# SDC_1.net
KiCad netlist of a schematic drawn in Altium Designer
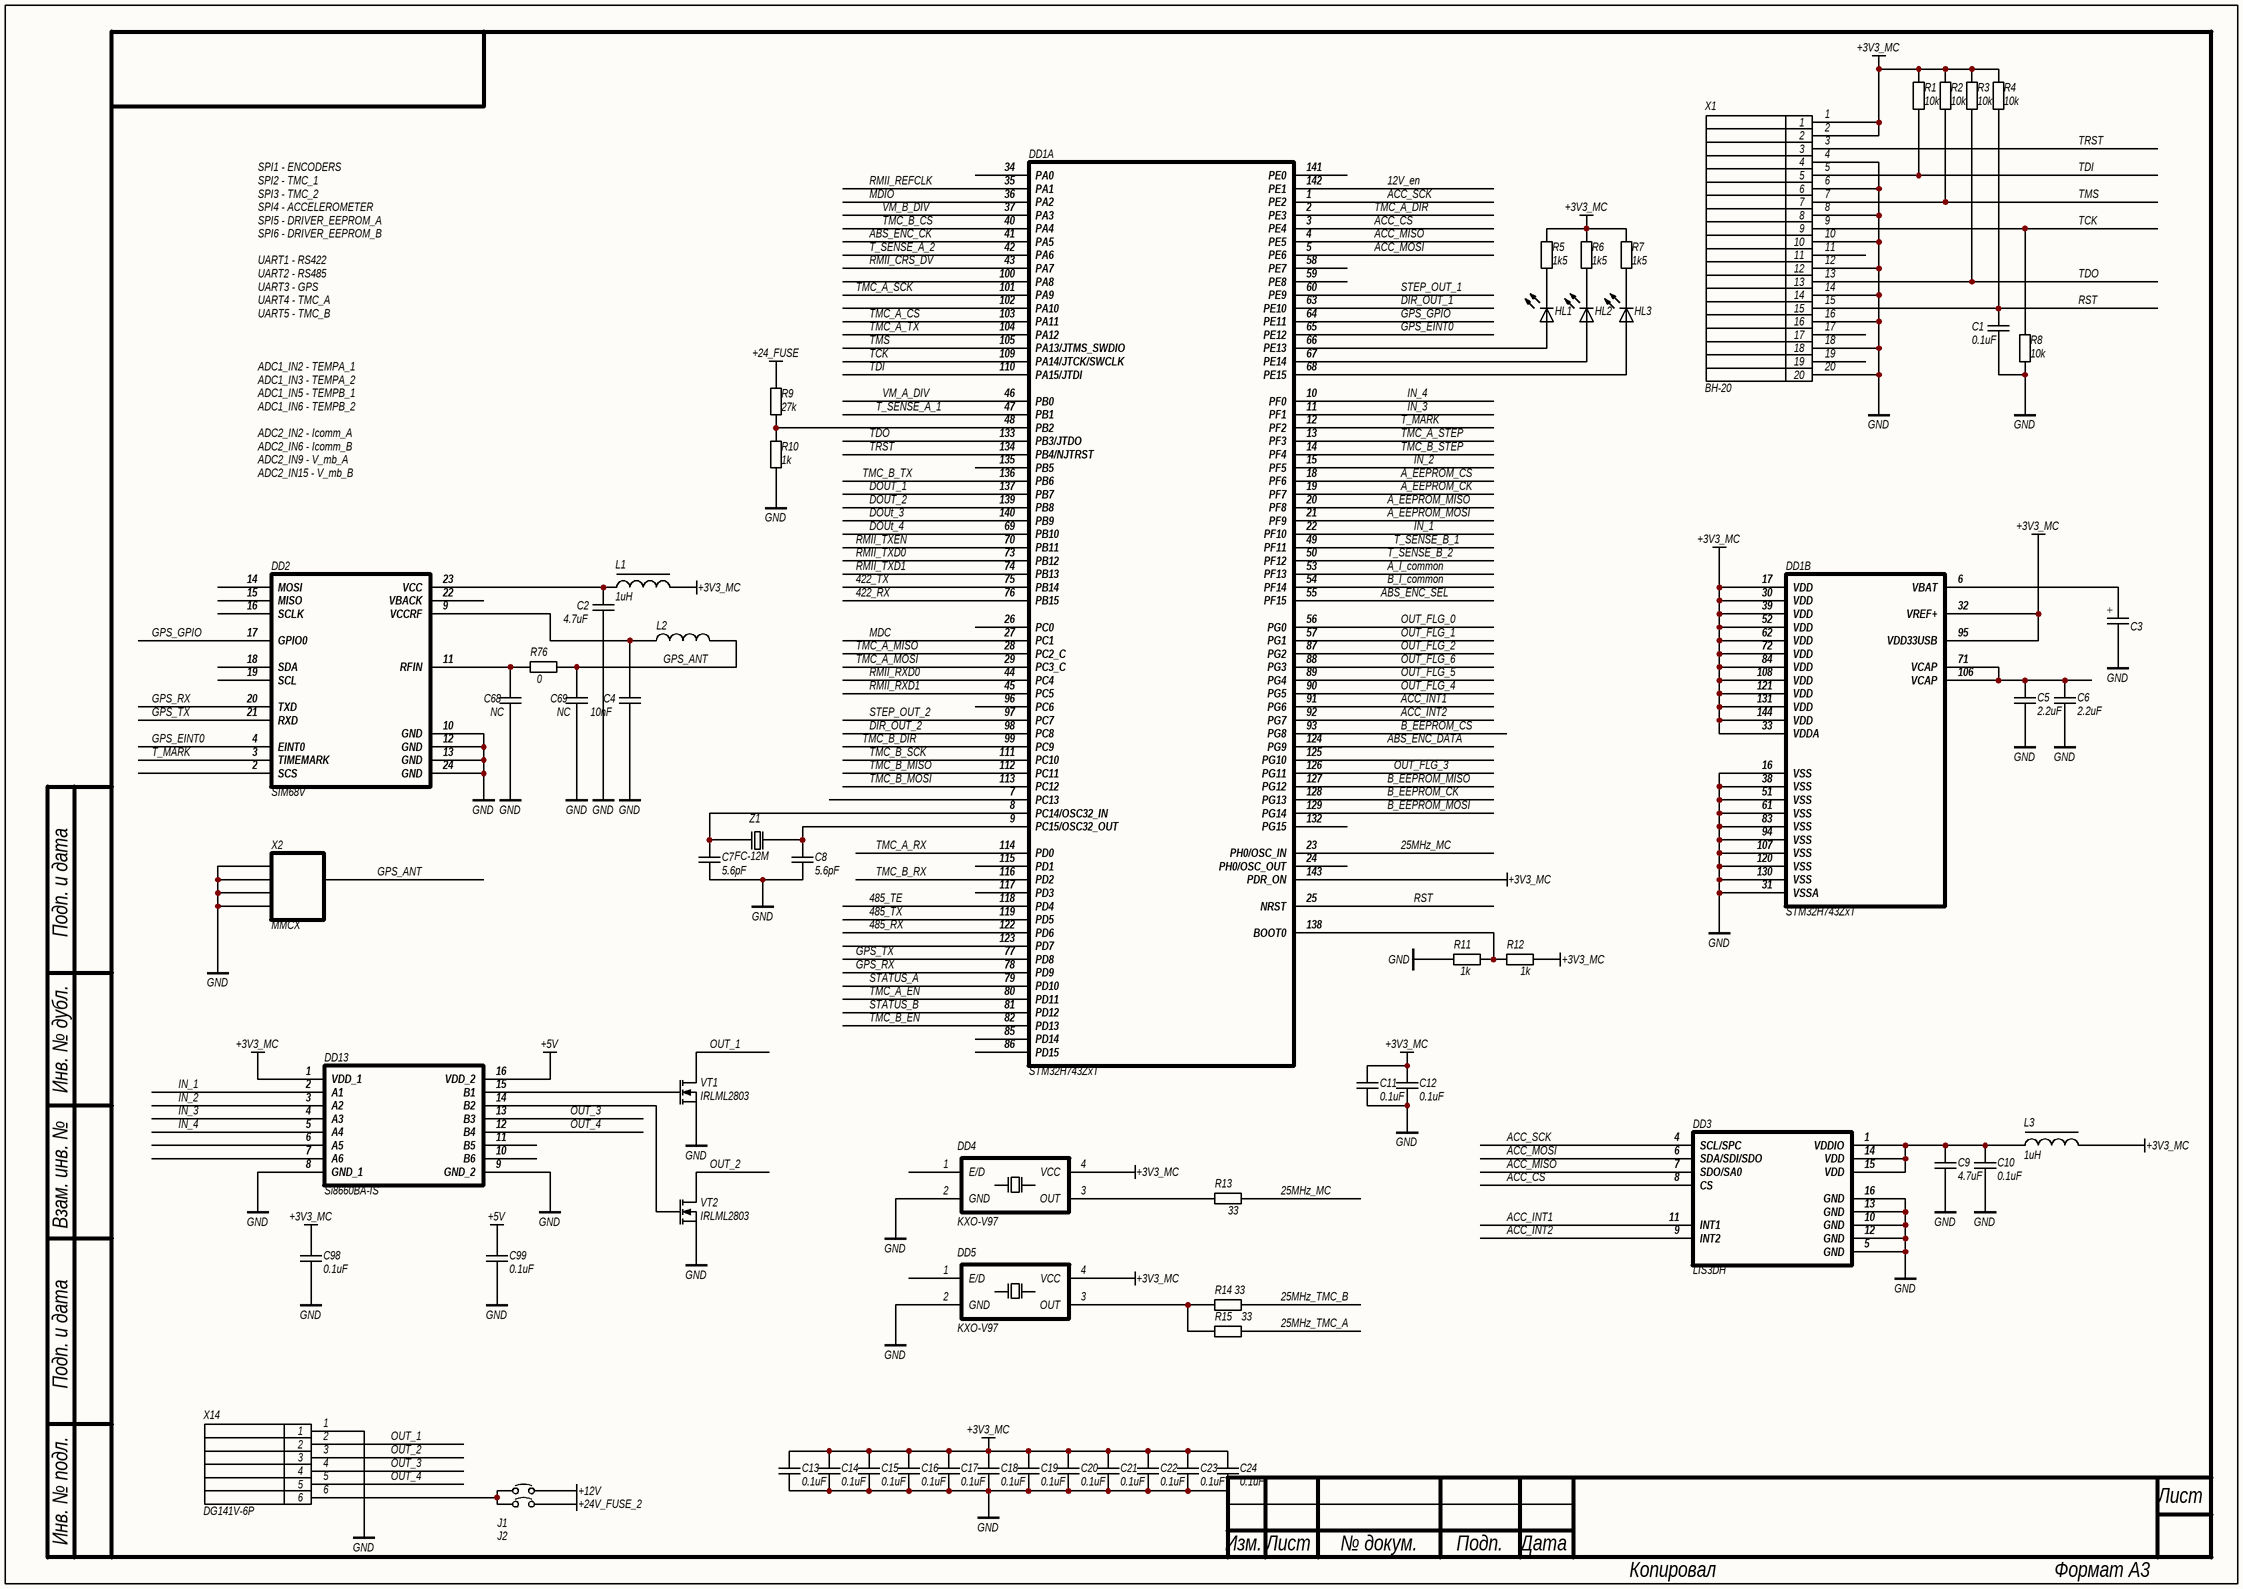
[diagram p0: SDC_1.SchDoc]

(export (version "E")
  (design (tool "Eeschema 10.0.6"))
  (components
    (comp (ref "C1")
      (value "0.1uF")
      (footprint "C0603")
      (description "SMD Capacitor")
      (fields (field (name "MANUFACTURER") "Murata") (field (name "TOLERANCE") "10%"))
      (libsource (lib "VKA") (part "CAP"))
    )
    (comp (ref "C2")
      (value "4.7uF")
      (footprint "C0603")
      (description "SMD Capacitor")
      (fields (field (name "MANUFACTURER") "Murata") (field (name "TOLERANCE") "10%"))
      (libsource (lib "VKA") (part "CAP"))
    )
    (comp (ref "C3")
      (value "KR-5R5H155-R")
      (footprint "KR-5R5H155-R")
      (description "Ionistor")
      (fields (field (name "MANUFACTURER") "Murata") (field (name "VOLTAGE") "5V"))
      (libsource (lib "VKA") (part "KR-5R5H155-R"))
    )
    (comp (ref "C4")
      (value "10nF")
      (footprint "C0603")
      (description "SMD Capacitor")
      (fields (field (name "MANUFACTURER") "Murata") (field (name "TOLERANCE") "10%"))
      (libsource (lib "VKA") (part "CAP"))
    )
    (comp (ref "C5")
      (value "2.2uF")
      (footprint "C0603")
      (description "SMD Capacitor")
      (fields (field (name "MANUFACTURER") "Murata") (field (name "TOLERANCE") "10%"))
      (libsource (lib "VKA") (part "CAP"))
    )
    (comp (ref "C6")
      (value "2.2uF")
      (footprint "C0603")
      (description "SMD Capacitor")
      (fields (field (name "MANUFACTURER") "Murata") (field (name "TOLERANCE") "10%"))
      (libsource (lib "VKA") (part "CAP"))
    )
    (comp (ref "C7")
      (value "5.6pF")
      (footprint "C0603")
      (description "SMD Capacitor")
      (fields (field (name "MANUFACTURER") "Murata") (field (name "TOLERANCE") "10%"))
      (libsource (lib "VKA") (part "CAP"))
    )
    (comp (ref "C8")
      (value "5.6pF")
      (footprint "C0603")
      (description "SMD Capacitor")
      (fields (field (name "MANUFACTURER") "Murata") (field (name "TOLERANCE") "10%"))
      (libsource (lib "VKA") (part "CAP"))
    )
    (comp (ref "C9")
      (value "4.7uF")
      (footprint "C0603")
      (description "SMD Capacitor")
      (fields (field (name "MANUFACTURER") "Murata") (field (name "TOLERANCE") "10%"))
      (libsource (lib "VKA") (part "CAP"))
    )
    (comp (ref "C10")
      (value "0.1uF")
      (footprint "C0603")
      (description "SMD Capacitor")
      (fields (field (name "MANUFACTURER") "Murata") (field (name "TOLERANCE") "10%"))
      (libsource (lib "VKA") (part "CAP"))
    )
    (comp (ref "C11")
      (value "0.1uF")
      (footprint "C0603")
      (description "SMD Capacitor")
      (fields (field (name "MANUFACTURER") "Murata") (field (name "TOLERANCE") "10%"))
      (libsource (lib "VKA") (part "CAP"))
    )
    (comp (ref "C12")
      (value "0.1uF")
      (footprint "C0603")
      (description "SMD Capacitor")
      (fields (field (name "MANUFACTURER") "Murata") (field (name "TOLERANCE") "10%"))
      (libsource (lib "VKA") (part "CAP"))
    )
    (comp (ref "C13")
      (value "0.1uF")
      (footprint "C0603")
      (description "SMD Capacitor")
      (fields (field (name "MANUFACTURER") "Murata") (field (name "TOLERANCE") "10%"))
      (libsource (lib "VKA") (part "CAP"))
    )
    (comp (ref "C14")
      (value "0.1uF")
      (footprint "C0603")
      (description "SMD Capacitor")
      (fields (field (name "MANUFACTURER") "Murata") (field (name "TOLERANCE") "10%"))
      (libsource (lib "VKA") (part "CAP"))
    )
    (comp (ref "C15")
      (value "0.1uF")
      (footprint "C0603")
      (description "SMD Capacitor")
      (fields (field (name "MANUFACTURER") "Murata") (field (name "TOLERANCE") "10%"))
      (libsource (lib "VKA") (part "CAP"))
    )
    (comp (ref "C16")
      (value "0.1uF")
      (footprint "C0603")
      (description "SMD Capacitor")
      (fields (field (name "MANUFACTURER") "Murata") (field (name "TOLERANCE") "10%"))
      (libsource (lib "VKA") (part "CAP"))
    )
    (comp (ref "C17")
      (value "0.1uF")
      (footprint "C0603")
      (description "SMD Capacitor")
      (fields (field (name "MANUFACTURER") "Murata") (field (name "TOLERANCE") "10%"))
      (libsource (lib "VKA") (part "CAP"))
    )
    (comp (ref "C18")
      (value "0.1uF")
      (footprint "C0603")
      (description "SMD Capacitor")
      (fields (field (name "MANUFACTURER") "Murata") (field (name "TOLERANCE") "10%"))
      (libsource (lib "VKA") (part "CAP"))
    )
    (comp (ref "C19")
      (value "0.1uF")
      (footprint "C0603")
      (description "SMD Capacitor")
      (fields (field (name "MANUFACTURER") "Murata") (field (name "TOLERANCE") "10%"))
      (libsource (lib "VKA") (part "CAP"))
    )
    (comp (ref "C20")
      (value "0.1uF")
      (footprint "C0603")
      (description "SMD Capacitor")
      (fields (field (name "MANUFACTURER") "Murata") (field (name "TOLERANCE") "10%"))
      (libsource (lib "VKA") (part "CAP"))
    )
    (comp (ref "C21")
      (value "0.1uF")
      (footprint "C0603")
      (description "SMD Capacitor")
      (fields (field (name "MANUFACTURER") "Murata") (field (name "TOLERANCE") "10%"))
      (libsource (lib "VKA") (part "CAP"))
    )
    (comp (ref "C22")
      (value "0.1uF")
      (footprint "C0603")
      (description "SMD Capacitor")
      (fields (field (name "MANUFACTURER") "Murata") (field (name "TOLERANCE") "10%"))
      (libsource (lib "VKA") (part "CAP"))
    )
    (comp (ref "C23")
      (value "0.1uF")
      (footprint "C0603")
      (description "SMD Capacitor")
      (fields (field (name "MANUFACTURER") "Murata") (field (name "TOLERANCE") "10%"))
      (libsource (lib "VKA") (part "CAP"))
    )
    (comp (ref "C24")
      (value "0.1uF")
      (footprint "C0603")
      (description "SMD Capacitor")
      (fields (field (name "MANUFACTURER") "Murata") (field (name "TOLERANCE") "10%"))
      (libsource (lib "VKA") (part "CAP"))
    )
    (comp (ref "C68")
      (value "NC")
      (footprint "C0603")
      (description "SMD Capacitor")
      (fields (field (name "MANUFACTURER") "Murata") (field (name "TOLERANCE") "10%"))
      (libsource (lib "VKA") (part "CAP"))
    )
    (comp (ref "C69")
      (value "NC")
      (footprint "C0603")
      (description "SMD Capacitor")
      (fields (field (name "MANUFACTURER") "Murata") (field (name "TOLERANCE") "10%"))
      (libsource (lib "VKA") (part "CAP"))
    )
    (comp (ref "C98")
      (value "0.1uF")
      (footprint "C0603")
      (description "SMD Capacitor")
      (fields (field (name "MANUFACTURER") "Murata") (field (name "TOLERANCE") "10%"))
      (libsource (lib "VKA") (part "CAP"))
    )
    (comp (ref "C99")
      (value "0.1uF")
      (footprint "C0603")
      (description "SMD Capacitor")
      (fields (field (name "MANUFACTURER") "Murata") (field (name "TOLERANCE") "10%"))
      (libsource (lib "VKA") (part "CAP"))
    )
    (comp (ref "DD1")
      (value "STM32H743ZxT")
      (footprint "STM-LQFP144_L")
      (description "ARM Cortex-M7, 480MHz, 32-bit MCU+FPU, 144-pin LQFP")
      (libsource (lib "VKA") (part "STM32H743ZxT"))
    )
    (comp (ref "DD2")
      (value "SIM68V")
      (footprint "SIM68M")
      (description "GPS module")
      (libsource (lib "VKA") (part "SIM68V"))
    )
    (comp (ref "DD3")
      (value "LIS3DH")
      (footprint "LGA-16")
      (description "Accelerometer")
      (libsource (lib "VKA") (part "LIS3DH"))
    )
    (comp (ref "DD4")
      (value "KXO-V97")
      (footprint "SO4-GEN")
      (description "KXO generator")
      (libsource (lib "VKA") (part "KXO-V97"))
    )
    (comp (ref "DD5")
      (value "KXO-V97")
      (footprint "SO4-GEN")
      (description "KXO generator")
      (libsource (lib "VKA") (part "KXO-V97"))
    )
    (comp (ref "DD13")
      (value "Si8660BA-IS")
      (footprint "SO-16_N")
      (description "digital isolator")
      (libsource (lib "VKA") (part "Si8660BA-IS"))
    )
    (comp (ref "HL1") (value "LED0603") (footprint "LED0603") (libsource (lib "VKA") (part "LED0603")))
    (comp (ref "HL2") (value "LED0603") (footprint "LED0603") (libsource (lib "VKA") (part "LED0603")))
    (comp (ref "HL3") (value "LED0603") (footprint "LED0603") (libsource (lib "VKA") (part "LED0603")))
    (comp (ref "J1") (value "JUMP") (footprint "JUMP") (libsource (lib "VKA") (part "JUMP")))
    (comp (ref "J2") (value "JUMP") (footprint "JUMP") (libsource (lib "VKA") (part "JUMP")))
    (comp (ref "L1")
      (value "1uH")
      (footprint "LQH32CN")
      (description "chip inductor")
      (fields (field (name "Comment") "LQH32CN"))
      (libsource (lib "VKA") (part "LQH32CN"))
    )
    (comp (ref "L2")
      (value "FerriteBead")
      (footprint "L0603")
      (description "SMD Chip ferrite bead 0603")
      (libsource (lib "VKA") (part "FerriteBead"))
    )
    (comp (ref "L3")
      (value "1uH")
      (footprint "LQH32CN")
      (description "chip inductor")
      (fields (field (name "Comment") "LQH32CN"))
      (libsource (lib "VKA") (part "LQH32CN"))
    )
    (comp (ref "R1")
      (value "10k")
      (footprint "R0603")
      (description "SMD Resistor")
      (fields (field (name "POWER") "0.062 Wt") (field (name "TOLERANCE") "5%"))
      (libsource (lib "") (part "RES_1"))
    )
    (comp (ref "R2")
      (value "10k")
      (footprint "R0603")
      (description "SMD Resistor")
      (fields (field (name "POWER") "0.062 Wt") (field (name "TOLERANCE") "5%"))
      (libsource (lib "") (part "RES_1"))
    )
    (comp (ref "R3")
      (value "10k")
      (footprint "R0603")
      (description "SMD Resistor")
      (fields (field (name "POWER") "0.062 Wt") (field (name "TOLERANCE") "5%"))
      (libsource (lib "") (part "RES_1"))
    )
    (comp (ref "R4")
      (value "10k")
      (footprint "R0603")
      (description "SMD Resistor")
      (fields (field (name "POWER") "0.062 Wt") (field (name "TOLERANCE") "5%"))
      (libsource (lib "") (part "RES_1"))
    )
    (comp (ref "R5")
      (value "1k5")
      (footprint "R0603")
      (description "SMD Resistor")
      (fields (field (name "POWER") "0.062 Wt") (field (name "TOLERANCE") "5%"))
      (libsource (lib "") (part "RES_1"))
    )
    (comp (ref "R6")
      (value "1k5")
      (footprint "R0603")
      (description "SMD Resistor")
      (fields (field (name "POWER") "0.062 Wt") (field (name "TOLERANCE") "5%"))
      (libsource (lib "") (part "RES_1"))
    )
    (comp (ref "R7")
      (value "1k5")
      (footprint "R0603")
      (description "SMD Resistor")
      (fields (field (name "POWER") "0.062 Wt") (field (name "TOLERANCE") "5%"))
      (libsource (lib "") (part "RES_1"))
    )
    (comp (ref "R8")
      (value "10k")
      (footprint "R0603")
      (description "SMD Resistor")
      (fields (field (name "POWER") "0.062 Wt") (field (name "TOLERANCE") "5%"))
      (libsource (lib "") (part "RES_1"))
    )
    (comp (ref "R9")
      (value "27k")
      (footprint "R0603")
      (description "SMD Resistor")
      (fields (field (name "POWER") "0.062 Wt") (field (name "TOLERANCE") "5%"))
      (libsource (lib "") (part "RES_2"))
    )
    (comp (ref "R10")
      (value "1k")
      (footprint "R0603")
      (description "SMD Resistor")
      (fields (field (name "POWER") "0.062 Wt") (field (name "TOLERANCE") "5%"))
      (libsource (lib "") (part "RES_2"))
    )
    (comp (ref "R11")
      (value "1k")
      (footprint "R0603")
      (description "SMD Resistor")
      (fields (field (name "POWER") "0.062 Wt") (field (name "TOLERANCE") "5%"))
      (libsource (lib "VKA") (part "RES"))
    )
    (comp (ref "R12")
      (value "1k")
      (footprint "R0603")
      (description "SMD Resistor")
      (fields (field (name "POWER") "0.062 Wt") (field (name "TOLERANCE") "5%"))
      (libsource (lib "VKA") (part "RES"))
    )
    (comp (ref "R13")
      (value "33")
      (footprint "R0603")
      (description "SMD Resistor")
      (fields (field (name "POWER") "0.062 Wt") (field (name "TOLERANCE") "5%"))
      (libsource (lib "VKA") (part "RES"))
    )
    (comp (ref "R14")
      (value "33")
      (footprint "R0603")
      (description "SMD Resistor")
      (fields (field (name "POWER") "0.062 Wt") (field (name "TOLERANCE") "5%"))
      (libsource (lib "VKA") (part "RES"))
    )
    (comp (ref "R15")
      (value "33")
      (footprint "R0603")
      (description "SMD Resistor")
      (fields (field (name "POWER") "0.062 Wt") (field (name "TOLERANCE") "5%"))
      (libsource (lib "VKA") (part "RES"))
    )
    (comp (ref "R76")
      (value "0")
      (footprint "R0603")
      (description "SMD Resistor")
      (fields (field (name "POWER") "0.062 Wt") (field (name "TOLERANCE") "5%"))
      (libsource (lib "VKA") (part "RES"))
    )
    (comp (ref "VT1")
      (value "IRLML2803")
      (footprint "SOT23")
      (description "n-channel fet")
      (libsource (lib "VKA") (part "IRLML2803"))
    )
    (comp (ref "VT2")
      (value "IRLML2803")
      (footprint "SOT23")
      (description "n-channel fet")
      (libsource (lib "VKA") (part "IRLML2803"))
    )
    (comp (ref "X1")
      (value "BH-20")
      (footprint "IDC-20(BH-20)")
      (libsource (lib "VKA") (part "IDC10x2_GOST"))
    )
    (comp (ref "X2")
      (value "MMCX")
      (footprint "MMCX")
      (description "Coaxial")
      (libsource (lib "VKA") (part "MMCX"))
    )
    (comp (ref "X14")
      (value "DG141V-6P")
      (footprint "DG141V-06P")
      (description "wire connector")
      (libsource (lib "VKA") (part "DG141V-6P"))
    )
    (comp (ref "Z1")
      (value "FC-12M")
      (footprint "FC-12M")
      (description "Crystal_32_768")
      (libsource (lib "VKA") (part "FC-12M"))
    )
  )
  (nets
    (net (code "1") (name "+3V3_MC") (class "Default")
      (node (ref "C11") (pin "2") (pinfunction "2_2") (pintype "passive"))
      (node (ref "C12") (pin "2") (pinfunction "2_2") (pintype "passive"))
      (node (ref "C13") (pin "2") (pinfunction "2_2") (pintype "passive"))
      (node (ref "C14") (pin "2") (pinfunction "2_2") (pintype "passive"))
      (node (ref "C15") (pin "2") (pinfunction "2_2") (pintype "passive"))
      (node (ref "C16") (pin "2") (pinfunction "2_2") (pintype "passive"))
      (node (ref "C17") (pin "2") (pinfunction "2_2") (pintype "passive"))
      (node (ref "C18") (pin "2") (pinfunction "2_2") (pintype "passive"))
      (node (ref "C19") (pin "2") (pinfunction "2_2") (pintype "passive"))
      (node (ref "C20") (pin "2") (pinfunction "2_2") (pintype "passive"))
      (node (ref "C21") (pin "2") (pinfunction "2_2") (pintype "passive"))
      (node (ref "C22") (pin "2") (pinfunction "2_2") (pintype "passive"))
      (node (ref "C23") (pin "2") (pinfunction "2_2") (pintype "passive"))
      (node (ref "C24") (pin "2") (pinfunction "2_2") (pintype "passive"))
      (node (ref "C98") (pin "2") (pinfunction "2_2") (pintype "passive"))
      (node (ref "DD1") (pin "108") (pinfunction "VDD_108") (pintype "passive"))
      (node (ref "DD1") (pin "121") (pinfunction "VDD_121") (pintype "passive"))
      (node (ref "DD1") (pin "131") (pinfunction "VDD_131") (pintype "passive"))
      (node (ref "DD1") (pin "143") (pinfunction "PDR_ON_143") (pintype "passive"))
      (node (ref "DD1") (pin "144") (pinfunction "VDD_144") (pintype "passive"))
      (node (ref "DD1") (pin "17") (pinfunction "VDD_17") (pintype "passive"))
      (node (ref "DD1") (pin "30") (pinfunction "VDD_30") (pintype "passive"))
      (node (ref "DD1") (pin "32") (pinfunction "VREF+_32") (pintype "passive"))
      (node (ref "DD1") (pin "33") (pinfunction "VDDA_33") (pintype "passive"))
      (node (ref "DD1") (pin "39") (pinfunction "VDD_39") (pintype "passive"))
      (node (ref "DD1") (pin "52") (pinfunction "VDD_52") (pintype "passive"))
      (node (ref "DD1") (pin "62") (pinfunction "VDD_62") (pintype "passive"))
      (node (ref "DD1") (pin "72") (pinfunction "VDD_72") (pintype "passive"))
      (node (ref "DD1") (pin "84") (pinfunction "VDD_84") (pintype "passive"))
      (node (ref "DD1") (pin "95") (pinfunction "VDD33USB_95") (pintype "passive"))
      (node (ref "DD13") (pin "1") (pinfunction "VDD_1_1") (pintype "passive"))
      (node (ref "DD4") (pin "4") (pinfunction "VCC_4") (pintype "passive"))
      (node (ref "DD5") (pin "4") (pinfunction "VCC_4") (pintype "passive"))
      (node (ref "L1") (pin "2") (pinfunction "2_2") (pintype "passive"))
      (node (ref "L3") (pin "2") (pinfunction "2_2") (pintype "passive"))
      (node (ref "R1") (pin "1") (pinfunction "1_1") (pintype "passive"))
      (node (ref "R12") (pin "1") (pinfunction "1_1") (pintype "passive"))
      (node (ref "R2") (pin "1") (pinfunction "1_1") (pintype "passive"))
      (node (ref "R3") (pin "1") (pinfunction "1_1") (pintype "passive"))
      (node (ref "R4") (pin "1") (pinfunction "1_1") (pintype "passive"))
      (node (ref "R5") (pin "1") (pinfunction "1_1") (pintype "passive"))
      (node (ref "R6") (pin "1") (pinfunction "1_1") (pintype "passive"))
      (node (ref "R7") (pin "1") (pinfunction "1_1") (pintype "passive"))
      (node (ref "X1") (pin "1") (pinfunction "1_1") (pintype "passive"))
      (node (ref "X1") (pin "2") (pinfunction "2_2") (pintype "passive"))
    )
    (net (code "2") (name "+5V") (class "Default")
      (node (ref "C99") (pin "2") (pinfunction "2_2") (pintype "passive"))
      (node (ref "DD13") (pin "16") (pinfunction "VDD_2_16") (pintype "passive"))
    )
    (net (code "3") (name "+12V") (class "Default")
      (node (ref "J1") (pin "2") (pinfunction "2_2") (pintype "passive"))
    )
    (net (code "4") (name "+24V_FUSE_2") (class "Default")
      (node (ref "J2") (pin "2") (pinfunction "2_2") (pintype "passive"))
    )
    (net (code "5") (name "+24_FUSE") (class "Default")
      (node (ref "R9") (pin "2") (pinfunction "2_2") (pintype "passive"))
    )
    (net (code "6") (name "/12V_en") (class "Default")
      (node (ref "DD1") (pin "142") (pinfunction "PE1_142") (pintype "passive"))
    )
    (net (code "7") (name "/25MHz_MC") (class "Default")
      (node (ref "DD1") (pin "23") (pinfunction "PH0/OSC_IN_23") (pintype "passive"))
      (node (ref "R13") (pin "1") (pinfunction "1_1") (pintype "passive"))
    )
    (net (code "8") (name "/25MHz_TMC_A") (class "Default")
      (node (ref "R15") (pin "1") (pinfunction "1_1") (pintype "passive"))
    )
    (net (code "9") (name "/25MHz_TMC_B") (class "Default")
      (node (ref "R14") (pin "1") (pinfunction "1_1") (pintype "passive"))
    )
    (net (code "10") (name "/422_RX") (class "Default")
      (node (ref "DD1") (pin "76") (pinfunction "PB15_76") (pintype "passive"))
    )
    (net (code "11") (name "/422_TX") (class "Default")
      (node (ref "DD1") (pin "75") (pinfunction "PB14_75") (pintype "passive"))
    )
    (net (code "12") (name "/485_RX") (class "Default")
      (node (ref "DD1") (pin "122") (pinfunction "PD6_122") (pintype "passive"))
    )
    (net (code "13") (name "/485_TE") (class "Default")
      (node (ref "DD1") (pin "118") (pinfunction "PD4_118") (pintype "passive"))
    )
    (net (code "14") (name "/485_TX") (class "Default")
      (node (ref "DD1") (pin "119") (pinfunction "PD5_119") (pintype "passive"))
    )
    (net (code "15") (name "/ABS_ENC_CK") (class "Default")
      (node (ref "DD1") (pin "41") (pinfunction "PA5_41") (pintype "passive"))
    )
    (net (code "16") (name "/ABS_ENC_DATA") (class "Default")
      (node (ref "DD1") (pin "124") (pinfunction "PG9_124") (pintype "passive"))
    )
    (net (code "17") (name "/ABS_ENC_SEL") (class "Default")
      (node (ref "DD1") (pin "55") (pinfunction "PF15_55") (pintype "passive"))
    )
    (net (code "18") (name "/ACC_CS") (class "Default")
      (node (ref "DD1") (pin "3") (pinfunction "PE4_3") (pintype "passive"))
      (node (ref "DD3") (pin "8") (pinfunction "CS_8") (pintype "passive"))
    )
    (net (code "19") (name "/ACC_INT1") (class "Default")
      (node (ref "DD1") (pin "91") (pinfunction "PG6_91") (pintype "passive"))
      (node (ref "DD3") (pin "11") (pinfunction "INT1_11") (pintype "passive"))
    )
    (net (code "20") (name "/ACC_INT2") (class "Default")
      (node (ref "DD1") (pin "92") (pinfunction "PG7_92") (pintype "passive"))
      (node (ref "DD3") (pin "9") (pinfunction "INT2_9") (pintype "passive"))
    )
    (net (code "21") (name "/ACC_MISO") (class "Default")
      (node (ref "DD1") (pin "4") (pinfunction "PE5_4") (pintype "passive"))
      (node (ref "DD3") (pin "7") (pinfunction "SDO/SA0_7") (pintype "passive"))
    )
    (net (code "22") (name "/ACC_MOSI") (class "Default")
      (node (ref "DD1") (pin "5") (pinfunction "PE6_5") (pintype "passive"))
      (node (ref "DD3") (pin "6") (pinfunction "SDA/SDI/SDO_6") (pintype "passive"))
    )
    (net (code "23") (name "/ACC_SCK") (class "Default")
      (node (ref "DD1") (pin "1") (pinfunction "PE2_1") (pintype "passive"))
      (node (ref "DD3") (pin "4") (pinfunction "SCL/SPC_4") (pintype "passive"))
    )
    (net (code "24") (name "/A_EEPROM_CK") (class "Default")
      (node (ref "DD1") (pin "19") (pinfunction "PF7_19") (pintype "passive"))
    )
    (net (code "25") (name "/A_EEPROM_CS") (class "Default")
      (node (ref "DD1") (pin "18") (pinfunction "PF6_18") (pintype "passive"))
    )
    (net (code "26") (name "/A_EEPROM_MISO") (class "Default")
      (node (ref "DD1") (pin "20") (pinfunction "PF8_20") (pintype "passive"))
    )
    (net (code "27") (name "/A_EEPROM_MOSI") (class "Default")
      (node (ref "DD1") (pin "21") (pinfunction "PF9_21") (pintype "passive"))
    )
    (net (code "28") (name "/A_I_common") (class "Default")
      (node (ref "DD1") (pin "53") (pinfunction "PF13_53") (pintype "passive"))
    )
    (net (code "29") (name "/B_EEPROM_CK") (class "Default")
      (node (ref "DD1") (pin "128") (pinfunction "PG13_128") (pintype "passive"))
    )
    (net (code "30") (name "/B_EEPROM_CS") (class "Default")
      (node (ref "DD1") (pin "93") (pinfunction "PG8_93") (pintype "passive"))
    )
    (net (code "31") (name "/B_EEPROM_MISO") (class "Default")
      (node (ref "DD1") (pin "127") (pinfunction "PG12_127") (pintype "passive"))
    )
    (net (code "32") (name "/B_EEPROM_MOSI") (class "Default")
      (node (ref "DD1") (pin "129") (pinfunction "PG14_129") (pintype "passive"))
    )
    (net (code "33") (name "/B_I_common") (class "Default")
      (node (ref "DD1") (pin "54") (pinfunction "PF14_54") (pintype "passive"))
    )
    (net (code "34") (name "/DIR_OUT_1") (class "Default")
      (node (ref "DD1") (pin "63") (pinfunction "PE10_63") (pintype "passive"))
    )
    (net (code "35") (name "/DIR_OUT_2") (class "Default")
      (node (ref "DD1") (pin "98") (pinfunction "PC8_98") (pintype "passive"))
    )
    (net (code "36") (name "/DOUT_1") (class "Default")
      (node (ref "DD1") (pin "137") (pinfunction "PB7_137") (pintype "passive"))
    )
    (net (code "37") (name "/DOUT_2") (class "Default")
      (node (ref "DD1") (pin "139") (pinfunction "PB8_139") (pintype "passive"))
    )
    (net (code "38") (name "/DOUt_3") (class "Default")
      (node (ref "DD1") (pin "140") (pinfunction "PB9_140") (pintype "passive"))
    )
    (net (code "39") (name "/DOUt_4") (class "Default")
      (node (ref "DD1") (pin "69") (pinfunction "PB10_69") (pintype "passive"))
    )
    (net (code "40") (name "/GPS_ANT") (class "Default")
      (node (ref "C69") (pin "2") (pinfunction "2_2") (pintype "passive"))
      (node (ref "L2") (pin "2") (pinfunction "2_2") (pintype "passive"))
      (node (ref "R76") (pin "1") (pinfunction "1_1") (pintype "passive"))
      (node (ref "X2") (pin "5") (pinfunction "SYG_5") (pintype "passive"))
    )
    (net (code "41") (name "/GPS_EINT0") (class "Default")
      (node (ref "DD1") (pin "65") (pinfunction "PE12_65") (pintype "passive"))
      (node (ref "DD2") (pin "4") (pinfunction "EINT0_4") (pintype "passive"))
    )
    (net (code "42") (name "/GPS_GPIO") (class "Default")
      (node (ref "DD1") (pin "64") (pinfunction "PE11_64") (pintype "passive"))
      (node (ref "DD2") (pin "17") (pinfunction "GPIO0_17") (pintype "passive"))
    )
    (net (code "43") (name "/GPS_RX") (class "Default")
      (node (ref "DD1") (pin "78") (pinfunction "PD9_78") (pintype "passive"))
      (node (ref "DD2") (pin "20") (pinfunction "TXD_20") (pintype "passive"))
    )
    (net (code "44") (name "/GPS_TX") (class "Default")
      (node (ref "DD1") (pin "77") (pinfunction "PD8_77") (pintype "passive"))
      (node (ref "DD2") (pin "21") (pinfunction "RXD_21") (pintype "passive"))
    )
    (net (code "45") (name "/IN_1") (class "Default")
      (node (ref "DD1") (pin "22") (pinfunction "PF10_22") (pintype "passive"))
      (node (ref "DD13") (pin "2") (pinfunction "A1_2") (pintype "passive"))
    )
    (net (code "46") (name "/IN_2") (class "Default")
      (node (ref "DD1") (pin "15") (pinfunction "PF5_15") (pintype "passive"))
      (node (ref "DD13") (pin "3") (pinfunction "A2_3") (pintype "passive"))
    )
    (net (code "47") (name "/IN_3") (class "Default")
      (node (ref "DD1") (pin "11") (pinfunction "PF1_11") (pintype "passive"))
      (node (ref "DD13") (pin "4") (pinfunction "A3_4") (pintype "passive"))
    )
    (net (code "48") (name "/IN_4") (class "Default")
      (node (ref "DD1") (pin "10") (pinfunction "PF0_10") (pintype "passive"))
      (node (ref "DD13") (pin "5") (pinfunction "A4_5") (pintype "passive"))
    )
    (net (code "49") (name "/MDC") (class "Default")
      (node (ref "DD1") (pin "27") (pinfunction "PC1_27") (pintype "passive"))
    )
    (net (code "50") (name "/MDIO") (class "Default")
      (node (ref "DD1") (pin "36") (pinfunction "PA2_36") (pintype "passive"))
    )
    (net (code "51") (name "/OUT_1") (class "Default")
      (node (ref "VT1") (pin "3") (pinfunction "D_3") (pintype "passive"))
      (node (ref "X14") (pin "2") (pinfunction "2_2") (pintype "passive"))
    )
    (net (code "52") (name "/OUT_2") (class "Default")
      (node (ref "VT2") (pin "3") (pinfunction "D_3") (pintype "passive"))
      (node (ref "X14") (pin "3") (pinfunction "3_3") (pintype "passive"))
    )
    (net (code "53") (name "/OUT_3") (class "Default")
      (node (ref "DD13") (pin "13") (pinfunction "B3_13") (pintype "passive"))
      (node (ref "X14") (pin "4") (pinfunction "4_4") (pintype "passive"))
    )
    (net (code "54") (name "/OUT_4") (class "Default")
      (node (ref "DD13") (pin "12") (pinfunction "B4_12") (pintype "passive"))
      (node (ref "X14") (pin "5") (pinfunction "5_5") (pintype "passive"))
    )
    (net (code "55") (name "/OUT_FLG_0") (class "Default")
      (node (ref "DD1") (pin "56") (pinfunction "PG0_56") (pintype "passive"))
    )
    (net (code "56") (name "/OUT_FLG_1") (class "Default")
      (node (ref "DD1") (pin "57") (pinfunction "PG1_57") (pintype "passive"))
    )
    (net (code "57") (name "/OUT_FLG_2") (class "Default")
      (node (ref "DD1") (pin "87") (pinfunction "PG2_87") (pintype "passive"))
    )
    (net (code "58") (name "/OUT_FLG_3") (class "Default")
      (node (ref "DD1") (pin "126") (pinfunction "PG11_126") (pintype "passive"))
    )
    (net (code "59") (name "/OUT_FLG_4") (class "Default")
      (node (ref "DD1") (pin "90") (pinfunction "PG5_90") (pintype "passive"))
    )
    (net (code "60") (name "/OUT_FLG_5") (class "Default")
      (node (ref "DD1") (pin "89") (pinfunction "PG4_89") (pintype "passive"))
    )
    (net (code "61") (name "/OUT_FLG_6") (class "Default")
      (node (ref "DD1") (pin "88") (pinfunction "PG3_88") (pintype "passive"))
    )
    (net (code "62") (name "/RMII_CRS_DV") (class "Default")
      (node (ref "DD1") (pin "43") (pinfunction "PA7_43") (pintype "passive"))
    )
    (net (code "63") (name "/RMII_REFCLK") (class "Default")
      (node (ref "DD1") (pin "35") (pinfunction "PA1_35") (pintype "passive"))
    )
    (net (code "64") (name "/RMII_RXD0") (class "Default")
      (node (ref "DD1") (pin "44") (pinfunction "PC4_44") (pintype "passive"))
    )
    (net (code "65") (name "/RMII_RXD1") (class "Default")
      (node (ref "DD1") (pin "45") (pinfunction "PC5_45") (pintype "passive"))
    )
    (net (code "66") (name "/RMII_TXD0") (class "Default")
      (node (ref "DD1") (pin "73") (pinfunction "PB12_73") (pintype "passive"))
    )
    (net (code "67") (name "/RMII_TXD1") (class "Default")
      (node (ref "DD1") (pin "74") (pinfunction "PB13_74") (pintype "passive"))
    )
    (net (code "68") (name "/RMII_TXEN") (class "Default")
      (node (ref "DD1") (pin "70") (pinfunction "PB11_70") (pintype "passive"))
    )
    (net (code "69") (name "/RST") (class "Default")
      (node (ref "C1") (pin "2") (pinfunction "2_2") (pintype "passive"))
      (node (ref "DD1") (pin "25") (pinfunction "NRST_25") (pintype "passive"))
      (node (ref "R4") (pin "2") (pinfunction "2_2") (pintype "passive"))
      (node (ref "X1") (pin "15") (pinfunction "15_15") (pintype "passive"))
    )
    (net (code "70") (name "/STATUS_A") (class "Default")
      (node (ref "DD1") (pin "79") (pinfunction "PD10_79") (pintype "passive"))
    )
    (net (code "71") (name "/STATUS_B") (class "Default")
      (node (ref "DD1") (pin "81") (pinfunction "PD12_81") (pintype "passive"))
    )
    (net (code "72") (name "/STEP_OUT_1") (class "Default")
      (node (ref "DD1") (pin "60") (pinfunction "PE9_60") (pintype "passive"))
    )
    (net (code "73") (name "/STEP_OUT_2") (class "Default")
      (node (ref "DD1") (pin "97") (pinfunction "PC7_97") (pintype "passive"))
    )
    (net (code "74") (name "/TCK") (class "Default")
      (node (ref "DD1") (pin "109") (pinfunction "PA14/JTCK/SWCLK_109") (pintype "passive"))
      (node (ref "R8") (pin "1") (pinfunction "1_1") (pintype "passive"))
      (node (ref "X1") (pin "9") (pinfunction "9_9") (pintype "passive"))
    )
    (net (code "75") (name "/TDI") (class "Default")
      (node (ref "DD1") (pin "110") (pinfunction "PA15/JTDI_110") (pintype "passive"))
      (node (ref "R1") (pin "2") (pinfunction "2_2") (pintype "passive"))
      (node (ref "X1") (pin "5") (pinfunction "5_5") (pintype "passive"))
    )
    (net (code "76") (name "/TDO") (class "Default")
      (node (ref "DD1") (pin "133") (pinfunction "PB3/JTDO_133") (pintype "passive"))
      (node (ref "R3") (pin "2") (pinfunction "2_2") (pintype "passive"))
      (node (ref "X1") (pin "13") (pinfunction "13_13") (pintype "passive"))
    )
    (net (code "77") (name "/TMC_A_CS") (class "Default")
      (node (ref "DD1") (pin "103") (pinfunction "PA11_103") (pintype "passive"))
    )
    (net (code "78") (name "/TMC_A_DIR") (class "Default")
      (node (ref "DD1") (pin "2") (pinfunction "PE3_2") (pintype "passive"))
    )
    (net (code "79") (name "/TMC_A_EN") (class "Default")
      (node (ref "DD1") (pin "80") (pinfunction "PD11_80") (pintype "passive"))
    )
    (net (code "80") (name "/TMC_A_MISO") (class "Default")
      (node (ref "DD1") (pin "28") (pinfunction "PC2_C_28") (pintype "passive"))
    )
    (net (code "81") (name "/TMC_A_MOSI") (class "Default")
      (node (ref "DD1") (pin "29") (pinfunction "PC3_C_29") (pintype "passive"))
    )
    (net (code "82") (name "/TMC_A_RX") (class "Default")
      (node (ref "DD1") (pin "114") (pinfunction "PD0_114") (pintype "passive"))
    )
    (net (code "83") (name "/TMC_A_SCK") (class "Default")
      (node (ref "DD1") (pin "101") (pinfunction "PA9_101") (pintype "passive"))
    )
    (net (code "84") (name "/TMC_A_STEP") (class "Default")
      (node (ref "DD1") (pin "13") (pinfunction "PF3_13") (pintype "passive"))
    )
    (net (code "85") (name "/TMC_A_TX") (class "Default")
      (node (ref "DD1") (pin "104") (pinfunction "PA12_104") (pintype "passive"))
    )
    (net (code "86") (name "/TMC_B_CS") (class "Default")
      (node (ref "DD1") (pin "40") (pinfunction "PA4_40") (pintype "passive"))
    )
    (net (code "87") (name "/TMC_B_DIR") (class "Default")
      (node (ref "DD1") (pin "99") (pinfunction "PC9_99") (pintype "passive"))
    )
    (net (code "88") (name "/TMC_B_EN") (class "Default")
      (node (ref "DD1") (pin "82") (pinfunction "PD13_82") (pintype "passive"))
    )
    (net (code "89") (name "/TMC_B_MISO") (class "Default")
      (node (ref "DD1") (pin "112") (pinfunction "PC11_112") (pintype "passive"))
    )
    (net (code "90") (name "/TMC_B_MOSI") (class "Default")
      (node (ref "DD1") (pin "113") (pinfunction "PC12_113") (pintype "passive"))
    )
    (net (code "91") (name "/TMC_B_RX") (class "Default")
      (node (ref "DD1") (pin "116") (pinfunction "PD2_116") (pintype "passive"))
    )
    (net (code "92") (name "/TMC_B_SCK") (class "Default")
      (node (ref "DD1") (pin "111") (pinfunction "PC10_111") (pintype "passive"))
    )
    (net (code "93") (name "/TMC_B_STEP") (class "Default")
      (node (ref "DD1") (pin "14") (pinfunction "PF4_14") (pintype "passive"))
    )
    (net (code "94") (name "/TMC_B_TX") (class "Default")
      (node (ref "DD1") (pin "136") (pinfunction "PB6_136") (pintype "passive"))
    )
    (net (code "95") (name "/TMS") (class "Default")
      (node (ref "DD1") (pin "105") (pinfunction "PA13/JTMS_SWDIO_105") (pintype "passive"))
      (node (ref "R2") (pin "2") (pinfunction "2_2") (pintype "passive"))
      (node (ref "X1") (pin "7") (pinfunction "7_7") (pintype "passive"))
    )
    (net (code "96") (name "/TRST") (class "Default")
      (node (ref "DD1") (pin "134") (pinfunction "PB4/NJTRST_134") (pintype "passive"))
      (node (ref "X1") (pin "3") (pinfunction "3_3") (pintype "passive"))
    )
    (net (code "97") (name "/T_MARK") (class "Default")
      (node (ref "DD1") (pin "12") (pinfunction "PF2_12") (pintype "passive"))
      (node (ref "DD2") (pin "3") (pinfunction "TIMEMARK_3") (pintype "passive"))
    )
    (net (code "98") (name "/T_SENSE_A_1") (class "Default")
      (node (ref "DD1") (pin "47") (pinfunction "PB1_47") (pintype "passive"))
    )
    (net (code "99") (name "/T_SENSE_A_2") (class "Default")
      (node (ref "DD1") (pin "42") (pinfunction "PA6_42") (pintype "passive"))
    )
    (net (code "100") (name "/T_SENSE_B_1") (class "Default")
      (node (ref "DD1") (pin "49") (pinfunction "PF11_49") (pintype "passive"))
    )
    (net (code "101") (name "/T_SENSE_B_2") (class "Default")
      (node (ref "DD1") (pin "50") (pinfunction "PF12_50") (pintype "passive"))
    )
    (net (code "102") (name "/VM_A_DIV") (class "Default")
      (node (ref "DD1") (pin "46") (pinfunction "PB0_46") (pintype "passive"))
    )
    (net (code "103") (name "/VM_B_DIV") (class "Default")
      (node (ref "DD1") (pin "37") (pinfunction "PA3_37") (pintype "passive"))
    )
    (net (code "104") (name "GND") (class "Default")
      (node (ref "C1") (pin "1") (pinfunction "1_1") (pintype "passive"))
      (node (ref "C10") (pin "1") (pinfunction "1_1") (pintype "passive"))
      (node (ref "C11") (pin "1") (pinfunction "1_1") (pintype "passive"))
      (node (ref "C12") (pin "1") (pinfunction "1_1") (pintype "passive"))
      (node (ref "C13") (pin "1") (pinfunction "1_1") (pintype "passive"))
      (node (ref "C14") (pin "1") (pinfunction "1_1") (pintype "passive"))
      (node (ref "C15") (pin "1") (pinfunction "1_1") (pintype "passive"))
      (node (ref "C16") (pin "1") (pinfunction "1_1") (pintype "passive"))
      (node (ref "C17") (pin "1") (pinfunction "1_1") (pintype "passive"))
      (node (ref "C18") (pin "1") (pinfunction "1_1") (pintype "passive"))
      (node (ref "C19") (pin "1") (pinfunction "1_1") (pintype "passive"))
      (node (ref "C2") (pin "1") (pinfunction "1_1") (pintype "passive"))
      (node (ref "C20") (pin "1") (pinfunction "1_1") (pintype "passive"))
      (node (ref "C21") (pin "1") (pinfunction "1_1") (pintype "passive"))
      (node (ref "C22") (pin "1") (pinfunction "1_1") (pintype "passive"))
      (node (ref "C23") (pin "1") (pinfunction "1_1") (pintype "passive"))
      (node (ref "C24") (pin "1") (pinfunction "1_1") (pintype "passive"))
      (node (ref "C3") (pin "1") (pinfunction "1_1") (pintype "passive"))
      (node (ref "C4") (pin "1") (pinfunction "1_1") (pintype "passive"))
      (node (ref "C5") (pin "1") (pinfunction "1_1") (pintype "passive"))
      (node (ref "C6") (pin "1") (pinfunction "1_1") (pintype "passive"))
      (node (ref "C68") (pin "1") (pinfunction "1_1") (pintype "passive"))
      (node (ref "C69") (pin "1") (pinfunction "1_1") (pintype "passive"))
      (node (ref "C7") (pin "1") (pinfunction "1_1") (pintype "passive"))
      (node (ref "C8") (pin "1") (pinfunction "1_1") (pintype "passive"))
      (node (ref "C9") (pin "1") (pinfunction "1_1") (pintype "passive"))
      (node (ref "C98") (pin "1") (pinfunction "1_1") (pintype "passive"))
      (node (ref "C99") (pin "1") (pinfunction "1_1") (pintype "passive"))
      (node (ref "DD1") (pin "107") (pinfunction "VSS_107") (pintype "passive"))
      (node (ref "DD1") (pin "120") (pinfunction "VSS_120") (pintype "passive"))
      (node (ref "DD1") (pin "130") (pinfunction "VSS_130") (pintype "passive"))
      (node (ref "DD1") (pin "16") (pinfunction "VSS_16") (pintype "passive"))
      (node (ref "DD1") (pin "31") (pinfunction "VSSA_31") (pintype "passive"))
      (node (ref "DD1") (pin "38") (pinfunction "VSS_38") (pintype "passive"))
      (node (ref "DD1") (pin "51") (pinfunction "VSS_51") (pintype "passive"))
      (node (ref "DD1") (pin "61") (pinfunction "VSS_61") (pintype "passive"))
      (node (ref "DD1") (pin "83") (pinfunction "VSS_83") (pintype "passive"))
      (node (ref "DD1") (pin "94") (pinfunction "VSS_94") (pintype "passive"))
      (node (ref "DD13") (pin "8") (pinfunction "GND_1_8") (pintype "passive"))
      (node (ref "DD13") (pin "9") (pinfunction "GND_2_9") (pintype "passive"))
      (node (ref "DD2") (pin "10") (pinfunction "GND_10") (pintype "passive"))
      (node (ref "DD2") (pin "12") (pinfunction "GND_12") (pintype "passive"))
      (node (ref "DD2") (pin "13") (pinfunction "GND_13") (pintype "passive"))
      (node (ref "DD2") (pin "24") (pinfunction "GND_24") (pintype "passive"))
      (node (ref "DD3") (pin "10") (pinfunction "GND_10") (pintype "passive"))
      (node (ref "DD3") (pin "12") (pinfunction "GND_12") (pintype "passive"))
      (node (ref "DD3") (pin "13") (pinfunction "GND_13") (pintype "passive"))
      (node (ref "DD3") (pin "16") (pinfunction "GND_16") (pintype "passive"))
      (node (ref "DD3") (pin "5") (pinfunction "GND_5") (pintype "passive"))
      (node (ref "DD4") (pin "2") (pinfunction "GND_2") (pintype "passive"))
      (node (ref "DD5") (pin "2") (pinfunction "GND_2") (pintype "passive"))
      (node (ref "R10") (pin "1") (pinfunction "1_1") (pintype "passive"))
      (node (ref "R11") (pin "2") (pinfunction "2_2") (pintype "passive"))
      (node (ref "R8") (pin "2") (pinfunction "2_2") (pintype "passive"))
      (node (ref "VT1") (pin "2") (pinfunction "S_2") (pintype "passive"))
      (node (ref "VT2") (pin "2") (pinfunction "S_2") (pintype "passive"))
      (node (ref "X1") (pin "10") (pinfunction "10_10") (pintype "passive"))
      (node (ref "X1") (pin "12") (pinfunction "12_12") (pintype "passive"))
      (node (ref "X1") (pin "14") (pinfunction "14_14") (pintype "passive"))
      (node (ref "X1") (pin "16") (pinfunction "16_16") (pintype "passive"))
      (node (ref "X1") (pin "18") (pinfunction "18_18") (pintype "passive"))
      (node (ref "X1") (pin "20") (pinfunction "20_20") (pintype "passive"))
      (node (ref "X1") (pin "4") (pinfunction "4_4") (pintype "passive"))
      (node (ref "X1") (pin "6") (pinfunction "6_6") (pintype "passive"))
      (node (ref "X1") (pin "8") (pinfunction "8_8") (pintype "passive"))
      (node (ref "X14") (pin "1") (pinfunction "1_1") (pintype "passive"))
      (node (ref "X2") (pin "1") (pinfunction "GND_1") (pintype "passive"))
      (node (ref "X2") (pin "2") (pinfunction "GND_2") (pintype "passive"))
      (node (ref "X2") (pin "3") (pinfunction "GND_3") (pintype "passive"))
      (node (ref "X2") (pin "4") (pinfunction "GND_4") (pintype "passive"))
    )
    (net (code "105") (name "Net-(C5-Pad2)") (class "Default")
      (node (ref "C5") (pin "2") (pinfunction "2_2") (pintype "passive"))
      (node (ref "C6") (pin "2") (pinfunction "2_2") (pintype "passive"))
      (node (ref "DD1") (pin "106") (pinfunction "VCAP_106") (pintype "passive"))
      (node (ref "DD1") (pin "71") (pinfunction "VCAP_71") (pintype "passive"))
    )
    (net (code "106") (name "Net-(DD1A-BOOT0)") (class "Default")
      (node (ref "DD1") (pin "138") (pinfunction "BOOT0_138") (pintype "passive"))
      (node (ref "R11") (pin "1") (pinfunction "1_1") (pintype "passive"))
      (node (ref "R12") (pin "2") (pinfunction "2_2") (pintype "passive"))
    )
    (net (code "107") (name "Net-(DD1A-PB2)") (class "Default")
      (node (ref "DD1") (pin "48") (pinfunction "PB2_48") (pintype "passive"))
      (node (ref "R10") (pin "2") (pinfunction "2_2") (pintype "passive"))
      (node (ref "R9") (pin "1") (pinfunction "1_1") (pintype "passive"))
    )
    (net (code "108") (name "Net-(DD1A-PC14{slash}OSC32_IN)") (class "Default")
      (node (ref "C7") (pin "2") (pinfunction "2_2") (pintype "passive"))
      (node (ref "DD1") (pin "8") (pinfunction "PC14/OSC32_IN_8") (pintype "passive"))
      (node (ref "Z1") (pin "1") (pinfunction "1_1") (pintype "passive"))
    )
    (net (code "109") (name "Net-(DD1A-PC15{slash}OSC32_OUT)") (class "Default")
      (node (ref "C8") (pin "2") (pinfunction "2_2") (pintype "passive"))
      (node (ref "DD1") (pin "9") (pinfunction "PC15/OSC32_OUT_9") (pintype "passive"))
      (node (ref "Z1") (pin "2") (pinfunction "2_2") (pintype "passive"))
    )
    (net (code "110") (name "Net-(DD1A-PE13)") (class "Default")
      (node (ref "DD1") (pin "66") (pinfunction "PE13_66") (pintype "passive"))
      (node (ref "HL1") (pin "1") (pinfunction "A_1") (pintype "passive"))
    )
    (net (code "111") (name "Net-(DD1A-PE14)") (class "Default")
      (node (ref "DD1") (pin "67") (pinfunction "PE14_67") (pintype "passive"))
      (node (ref "HL2") (pin "1") (pinfunction "A_1") (pintype "passive"))
    )
    (net (code "112") (name "Net-(DD1A-PE15)") (class "Default")
      (node (ref "DD1") (pin "68") (pinfunction "PE15_68") (pintype "passive"))
      (node (ref "HL3") (pin "1") (pinfunction "A_1") (pintype "passive"))
    )
    (net (code "113") (name "Net-(DD1B-VBAT)") (class "Default")
      (node (ref "C3") (pin "2") (pinfunction "2_2") (pintype "passive"))
      (node (ref "DD1") (pin "6") (pinfunction "VBAT_6") (pintype "passive"))
    )
    (net (code "114") (name "Net-(DD2-RFIN)") (class "Default")
      (node (ref "C68") (pin "2") (pinfunction "2_2") (pintype "passive"))
      (node (ref "DD2") (pin "11") (pinfunction "RFIN_11") (pintype "passive"))
      (node (ref "R76") (pin "2") (pinfunction "2_2") (pintype "passive"))
    )
    (net (code "115") (name "Net-(DD2-VCC)") (class "Default")
      (node (ref "C2") (pin "2") (pinfunction "2_2") (pintype "passive"))
      (node (ref "DD2") (pin "23") (pinfunction "VCC_23") (pintype "passive"))
      (node (ref "L1") (pin "1") (pinfunction "1_1") (pintype "passive"))
    )
    (net (code "116") (name "Net-(DD2-VCCRF)") (class "Default")
      (node (ref "C4") (pin "2") (pinfunction "2_2") (pintype "passive"))
      (node (ref "DD2") (pin "9") (pinfunction "VCCRF_9") (pintype "passive"))
      (node (ref "L2") (pin "1") (pinfunction "1_1") (pintype "passive"))
    )
    (net (code "117") (name "Net-(DD3-VDDIO)") (class "Default")
      (node (ref "C10") (pin "2") (pinfunction "2_2") (pintype "passive"))
      (node (ref "C9") (pin "2") (pinfunction "2_2") (pintype "passive"))
      (node (ref "DD3") (pin "1") (pinfunction "VDDIO_1") (pintype "passive"))
      (node (ref "DD3") (pin "14") (pinfunction "VDD_14") (pintype "passive"))
      (node (ref "DD3") (pin "15") (pinfunction "VDD_15") (pintype "passive"))
      (node (ref "L3") (pin "1") (pinfunction "1_1") (pintype "passive"))
    )
    (net (code "118") (name "Net-(DD4-OUT)") (class "Default")
      (node (ref "DD4") (pin "3") (pinfunction "OUT_3") (pintype "passive"))
      (node (ref "R13") (pin "2") (pinfunction "2_2") (pintype "passive"))
    )
    (net (code "119") (name "Net-(DD5-OUT)") (class "Default")
      (node (ref "DD5") (pin "3") (pinfunction "OUT_3") (pintype "passive"))
      (node (ref "R14") (pin "2") (pinfunction "2_2") (pintype "passive"))
      (node (ref "R15") (pin "2") (pinfunction "2_2") (pintype "passive"))
    )
    (net (code "120") (name "Net-(DD13-B1)") (class "Default")
      (node (ref "DD13") (pin "15") (pinfunction "B1_15") (pintype "passive"))
      (node (ref "VT1") (pin "1") (pinfunction "G_1") (pintype "passive"))
    )
    (net (code "121") (name "Net-(DD13-B2)") (class "Default")
      (node (ref "DD13") (pin "14") (pinfunction "B2_14") (pintype "passive"))
      (node (ref "VT2") (pin "1") (pinfunction "G_1") (pintype "passive"))
    )
    (net (code "122") (name "Net-(HL1-K)") (class "Default")
      (node (ref "HL1") (pin "2") (pinfunction "K_2") (pintype "passive"))
      (node (ref "R5") (pin "2") (pinfunction "2_2") (pintype "passive"))
    )
    (net (code "123") (name "Net-(HL2-K)") (class "Default")
      (node (ref "HL2") (pin "2") (pinfunction "K_2") (pintype "passive"))
      (node (ref "R6") (pin "2") (pinfunction "2_2") (pintype "passive"))
    )
    (net (code "124") (name "Net-(HL3-K)") (class "Default")
      (node (ref "HL3") (pin "2") (pinfunction "K_2") (pintype "passive"))
      (node (ref "R7") (pin "2") (pinfunction "2_2") (pintype "passive"))
    )
    (net (code "125") (name "Net-(J1-Pad1)") (class "Default")
      (node (ref "J1") (pin "1") (pinfunction "1_1") (pintype "passive"))
      (node (ref "J2") (pin "1") (pinfunction "1_1") (pintype "passive"))
      (node (ref "X14") (pin "6") (pinfunction "6_6") (pintype "passive"))
    )
    (net (code "126") (name "unconnected-(DD1A-PA0-Pad34)") (class "Default")
      (node (ref "DD1") (pin "34") (pinfunction "PA0_34") (pintype "passive"))
    )
    (net (code "127") (name "unconnected-(DD1A-PA8-Pad100)") (class "Default")
      (node (ref "DD1") (pin "100") (pinfunction "PA8_100") (pintype "passive"))
    )
    (net (code "128") (name "unconnected-(DD1A-PA10-Pad102)") (class "Default")
      (node (ref "DD1") (pin "102") (pinfunction "PA10_102") (pintype "passive"))
    )
    (net (code "129") (name "unconnected-(DD1A-PB5-Pad135)") (class "Default")
      (node (ref "DD1") (pin "135") (pinfunction "PB5_135") (pintype "passive"))
    )
    (net (code "130") (name "unconnected-(DD1A-PC0-Pad26)") (class "Default")
      (node (ref "DD1") (pin "26") (pinfunction "PC0_26") (pintype "passive"))
    )
    (net (code "131") (name "unconnected-(DD1A-PC6-Pad96)") (class "Default")
      (node (ref "DD1") (pin "96") (pinfunction "PC6_96") (pintype "passive"))
    )
    (net (code "132") (name "unconnected-(DD1A-PC13-Pad7)") (class "Default")
      (node (ref "DD1") (pin "7") (pinfunction "PC13_7") (pintype "passive"))
    )
    (net (code "133") (name "unconnected-(DD1A-PD1-Pad115)") (class "Default")
      (node (ref "DD1") (pin "115") (pinfunction "PD1_115") (pintype "passive"))
    )
    (net (code "134") (name "unconnected-(DD1A-PD3-Pad117)") (class "Default")
      (node (ref "DD1") (pin "117") (pinfunction "PD3_117") (pintype "passive"))
    )
    (net (code "135") (name "unconnected-(DD1A-PD7-Pad123)") (class "Default")
      (node (ref "DD1") (pin "123") (pinfunction "PD7_123") (pintype "passive"))
    )
    (net (code "136") (name "unconnected-(DD1A-PD14-Pad85)") (class "Default")
      (node (ref "DD1") (pin "85") (pinfunction "PD14_85") (pintype "passive"))
    )
    (net (code "137") (name "unconnected-(DD1A-PD15-Pad86)") (class "Default")
      (node (ref "DD1") (pin "86") (pinfunction "PD15_86") (pintype "passive"))
    )
    (net (code "138") (name "unconnected-(DD1A-PE0-Pad141)") (class "Default")
      (node (ref "DD1") (pin "141") (pinfunction "PE0_141") (pintype "passive"))
    )
    (net (code "139") (name "unconnected-(DD1A-PE7-Pad58)") (class "Default")
      (node (ref "DD1") (pin "58") (pinfunction "PE7_58") (pintype "passive"))
    )
    (net (code "140") (name "unconnected-(DD1A-PE8-Pad59)") (class "Default")
      (node (ref "DD1") (pin "59") (pinfunction "PE8_59") (pintype "passive"))
    )
    (net (code "141") (name "unconnected-(DD1A-PG10-Pad125)") (class "Default")
      (node (ref "DD1") (pin "125") (pinfunction "PG10_125") (pintype "passive"))
    )
    (net (code "142") (name "unconnected-(DD1A-PG15-Pad132)") (class "Default")
      (node (ref "DD1") (pin "132") (pinfunction "PG15_132") (pintype "passive"))
    )
    (net (code "143") (name "unconnected-(DD1A-PH0{slash}OSC_OUT-Pad24)") (class "Default")
      (node (ref "DD1") (pin "24") (pinfunction "PH0/OSC_OUT_24") (pintype "passive"))
    )
    (net (code "144") (name "unconnected-(DD2-MISO-Pad15)") (class "Default")
      (node (ref "DD2") (pin "15") (pinfunction "MISO_15") (pintype "passive"))
    )
    (net (code "145") (name "unconnected-(DD2-MOSI-Pad14)") (class "Default")
      (node (ref "DD2") (pin "14") (pinfunction "MOSI_14") (pintype "passive"))
    )
    (net (code "146") (name "unconnected-(DD2-SCL-Pad19)") (class "Default")
      (node (ref "DD2") (pin "19") (pinfunction "SCL_19") (pintype "passive"))
    )
    (net (code "147") (name "unconnected-(DD2-SCLK-Pad16)") (class "Default")
      (node (ref "DD2") (pin "16") (pinfunction "SCLK_16") (pintype "passive"))
    )
    (net (code "148") (name "unconnected-(DD2-SCS-Pad2)") (class "Default")
      (node (ref "DD2") (pin "2") (pinfunction "SCS_2") (pintype "passive"))
    )
    (net (code "149") (name "unconnected-(DD2-SDA-Pad18)") (class "Default")
      (node (ref "DD2") (pin "18") (pinfunction "SDA_18") (pintype "passive"))
    )
    (net (code "150") (name "unconnected-(DD2-VBACK-Pad22)") (class "Default")
      (node (ref "DD2") (pin "22") (pinfunction "VBACK_22") (pintype "passive"))
    )
    (net (code "151") (name "unconnected-(DD4-E{slash}D-Pad1)") (class "Default")
      (node (ref "DD4") (pin "1") (pinfunction "E/D_1") (pintype "passive"))
    )
    (net (code "152") (name "unconnected-(DD5-E{slash}D-Pad1)") (class "Default")
      (node (ref "DD5") (pin "1") (pinfunction "E/D_1") (pintype "passive"))
    )
    (net (code "153") (name "unconnected-(DD13-A5-Pad6)") (class "Default")
      (node (ref "DD13") (pin "6") (pinfunction "A5_6") (pintype "passive"))
    )
    (net (code "154") (name "unconnected-(DD13-A6-Pad7)") (class "Default")
      (node (ref "DD13") (pin "7") (pinfunction "A6_7") (pintype "passive"))
    )
    (net (code "155") (name "unconnected-(DD13-B5-Pad11)") (class "Default")
      (node (ref "DD13") (pin "11") (pinfunction "B5_11") (pintype "passive"))
    )
    (net (code "156") (name "unconnected-(DD13-B6-Pad10)") (class "Default")
      (node (ref "DD13") (pin "10") (pinfunction "B6_10") (pintype "passive"))
    )
    (net (code "157") (name "unconnected-(X1-Pad11)") (class "Default")
      (node (ref "X1") (pin "11") (pinfunction "11_11") (pintype "passive"))
    )
    (net (code "158") (name "unconnected-(X1-Pad17)") (class "Default")
      (node (ref "X1") (pin "17") (pinfunction "17_17") (pintype "passive"))
    )
    (net (code "159") (name "unconnected-(X1-Pad19)") (class "Default")
      (node (ref "X1") (pin "19") (pinfunction "19_19") (pintype "passive"))
    )
  )
)
